# trackuino-shield.net
KiCad netlist of a schematic drawn in EAGLE
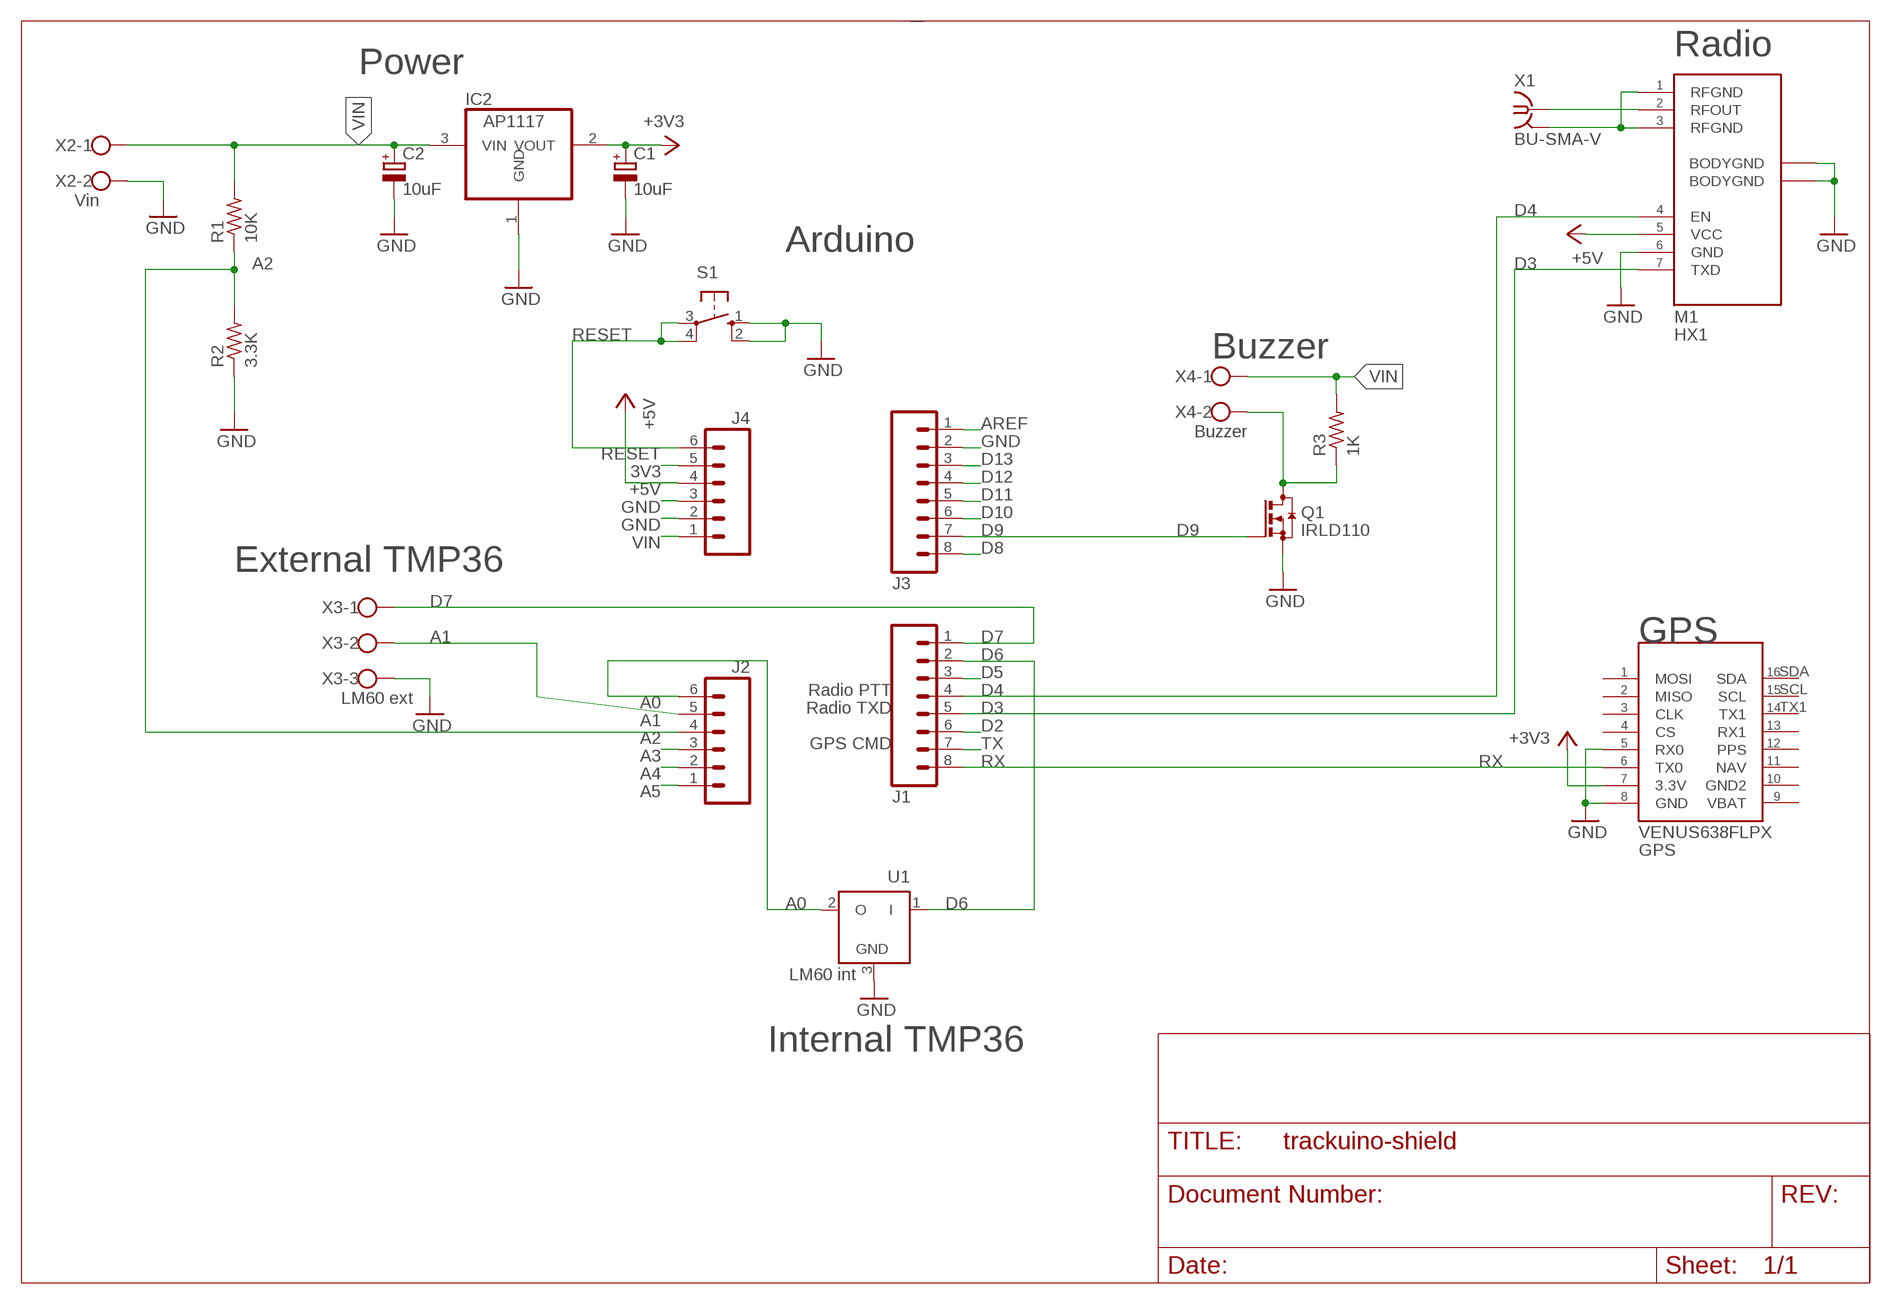
[diagram p0: schematic, sheet 1]

(export (version "E")
  (design (tool "Eeschema 10.0.6"))
  (components
    (comp (ref "C1")
      (value "10uF")
      (footprint "eagle-import:E2,5-5")
      (libsource (lib "eagle-import") (part "CPOL-EUE2.5-5"))
    )
    (comp (ref "C2")
      (value "10uF")
      (footprint "eagle-import:E2,5-5")
      (libsource (lib "eagle-import") (part "CPOL-EUE2.5-5"))
    )
    (comp (ref "GPS")
      (value "VENUS638FLPX")
      (footprint "eagle-import:VENUS638FLPX")
      (libsource (lib "eagle-import") (part "VENUS638FLPX"))
    )
    (comp (ref "IC2")
      (value "AP1117")
      (footprint "eagle-import:TO220-3")
      (libsource (lib "eagle-import") (part "AP1117"))
    )
    (comp (ref "J1")
      (value "M081X08")
      (footprint "eagle-import:1X08")
      (libsource (lib "eagle-import") (part "M081X08"))
    )
    (comp (ref "J2")
      (value "M06SIP")
      (footprint "eagle-import:1X06")
      (libsource (lib "eagle-import") (part "M06SIP"))
    )
    (comp (ref "J3")
      (value "M081X08")
      (footprint "eagle-import:1X08")
      (libsource (lib "eagle-import") (part "M081X08"))
    )
    (comp (ref "J4")
      (value "M06SIP")
      (footprint "eagle-import:1X06")
      (libsource (lib "eagle-import") (part "M06SIP"))
    )
    (comp (ref "M1")
      (value "HX1")
      (footprint "eagle-import:HX1")
      (libsource (lib "eagle-import") (part "HX1"))
    )
    (comp (ref "Q1")
      (value "IRLD110")
      (footprint "eagle-import:HVMDIP")
      (libsource (lib "eagle-import") (part "IRLD110"))
    )
    (comp (ref "R1")
      (value "10K")
      (footprint "eagle-import:0207_7")
      (libsource (lib "eagle-import") (part "R-US_0207/7"))
    )
    (comp (ref "R2")
      (value "3.3K")
      (footprint "eagle-import:0207_7")
      (libsource (lib "eagle-import") (part "R-US_0207/7"))
    )
    (comp (ref "R3")
      (value "1K")
      (footprint "eagle-import:0207_7")
      (libsource (lib "eagle-import") (part "R-US_0207/7"))
    )
    (comp (ref "S1")
      (value "10-XX")
      (footprint "eagle-import:B3F-10XX")
      (libsource (lib "eagle-import") (part "10-XX"))
    )
    (comp (ref "U1")
      (value "LM60 int")
      (footprint "eagle-import:TO92")
      (libsource (lib "eagle-import") (part "LM60"))
    )
    (comp (ref "X1")
      (value "BU-SMA-V")
      (footprint "eagle-import:BU-SMA-V")
      (libsource (lib "eagle-import") (part "BU-SMA-V"))
    )
    (comp (ref "X2")
      (value "Vin")
      (footprint "eagle-import:W237-102")
      (fields (field (name "MPN") "237-102"))
      (libsource (lib "eagle-import") (part "W237-102"))
    )
    (comp (ref "X3")
      (value "LM60 ext")
      (footprint "eagle-import:W237-103")
      (fields (field (name "MPN") "237-103"))
      (libsource (lib "eagle-import") (part "W237-103"))
    )
    (comp (ref "X4")
      (value "Buzzer")
      (footprint "eagle-import:W237-102")
      (fields (field (name "MPN") "237-102"))
      (libsource (lib "eagle-import") (part "W237-102"))
    )
  )
  (nets
    (net (code "1") (name "+3V3") (class "Default")
      (node (ref "C1") (pin "+") (pinfunction "+_+") (pintype "passive"))
      (node (ref "GPS") (pin "3.3V") (pinfunction "3.3V_3.3V") (pintype "bidirectional"))
      (node (ref "IC2") (pin "2") (pinfunction "VOUT_2") (pintype "output"))
    )
    (net (code "2") (name "+5V") (class "Default")
      (node (ref "J4") (pin "4") (pinfunction "4_4") (pintype "passive"))
      (node (ref "M1") (pin "VCC") (pinfunction "VCC_VCC") (pintype "bidirectional"))
    )
    (net (code "3") (name "/3V3") (class "Default")
      (node (ref "J4") (pin "5") (pinfunction "5_5") (pintype "passive"))
    )
    (net (code "4") (name "/A0") (class "Default")
      (node (ref "J2") (pin "6") (pinfunction "6_6") (pintype "passive"))
      (node (ref "U1") (pin "2") (pinfunction "O_2") (pintype "input"))
    )
    (net (code "5") (name "/A1") (class "Default")
      (node (ref "J2") (pin "5") (pinfunction "5_5") (pintype "passive"))
      (node (ref "X3") (pin "2") (pinfunction "KL_2") (pintype "passive"))
    )
    (net (code "6") (name "/A2") (class "Default")
      (node (ref "J2") (pin "4") (pinfunction "4_4") (pintype "passive"))
      (node (ref "R1") (pin "1") (pinfunction "1_1") (pintype "passive"))
      (node (ref "R2") (pin "2") (pinfunction "2_2") (pintype "passive"))
    )
    (net (code "7") (name "/A3") (class "Default")
      (node (ref "J2") (pin "3") (pinfunction "3_3") (pintype "passive"))
    )
    (net (code "8") (name "/A4") (class "Default")
      (node (ref "J2") (pin "2") (pinfunction "2_2") (pintype "passive"))
    )
    (net (code "9") (name "/A5") (class "Default")
      (node (ref "J2") (pin "1") (pinfunction "1_1") (pintype "passive"))
    )
    (net (code "10") (name "/AREF") (class "Default")
      (node (ref "J3") (pin "1") (pinfunction "1_1") (pintype "passive"))
    )
    (net (code "11") (name "/D2") (class "Default")
      (node (ref "J1") (pin "6") (pinfunction "6_6") (pintype "passive"))
    )
    (net (code "12") (name "/D3") (class "Default")
      (node (ref "J1") (pin "5") (pinfunction "5_5") (pintype "passive"))
      (node (ref "M1") (pin "TXD") (pinfunction "TXD_TXD") (pintype "bidirectional"))
    )
    (net (code "13") (name "/D4") (class "Default")
      (node (ref "J1") (pin "4") (pinfunction "4_4") (pintype "passive"))
      (node (ref "M1") (pin "EN") (pinfunction "EN_EN") (pintype "bidirectional"))
    )
    (net (code "14") (name "/D5") (class "Default")
      (node (ref "J1") (pin "3") (pinfunction "3_3") (pintype "passive"))
    )
    (net (code "15") (name "/D6") (class "Default")
      (node (ref "J1") (pin "2") (pinfunction "2_2") (pintype "passive"))
      (node (ref "U1") (pin "1") (pinfunction "I_1") (pintype "input"))
    )
    (net (code "16") (name "/D7") (class "Default")
      (node (ref "J1") (pin "1") (pinfunction "1_1") (pintype "passive"))
      (node (ref "X3") (pin "1") (pinfunction "KL_1") (pintype "passive"))
    )
    (net (code "17") (name "/D8") (class "Default")
      (node (ref "J3") (pin "8") (pinfunction "8_8") (pintype "passive"))
    )
    (net (code "18") (name "/D9") (class "Default")
      (node (ref "J3") (pin "7") (pinfunction "7_7") (pintype "passive"))
      (node (ref "Q1") (pin "G") (pinfunction "G_G") (pintype "passive"))
    )
    (net (code "19") (name "/D10") (class "Default")
      (node (ref "J3") (pin "6") (pinfunction "6_6") (pintype "passive"))
    )
    (net (code "20") (name "/D11") (class "Default")
      (node (ref "J3") (pin "5") (pinfunction "5_5") (pintype "passive"))
    )
    (net (code "21") (name "/D12") (class "Default")
      (node (ref "J3") (pin "4") (pinfunction "4_4") (pintype "passive"))
    )
    (net (code "22") (name "/D13") (class "Default")
      (node (ref "J3") (pin "3") (pinfunction "3_3") (pintype "passive"))
    )
    (net (code "23") (name "/RESET") (class "Default")
      (node (ref "J4") (pin "6") (pinfunction "6_6") (pintype "passive"))
      (node (ref "S1") (pin "3") (pinfunction "P_3") (pintype "passive"))
      (node (ref "S1") (pin "4") (pinfunction "P1_4") (pintype "passive"))
    )
    (net (code "24") (name "/RX") (class "Default")
      (node (ref "GPS") (pin "TX0") (pinfunction "TX0_TX0") (pintype "bidirectional"))
      (node (ref "J1") (pin "8") (pinfunction "8_8") (pintype "passive"))
    )
    (net (code "25") (name "/TX") (class "Default")
      (node (ref "J1") (pin "7") (pinfunction "7_7") (pintype "passive"))
    )
    (net (code "26") (name "GND") (class "Default")
      (node (ref "C1") (pin "-") (pinfunction "-_-") (pintype "passive"))
      (node (ref "C2") (pin "-") (pinfunction "-_-") (pintype "passive"))
      (node (ref "GPS") (pin "GND") (pinfunction "GND_GND") (pintype "bidirectional"))
      (node (ref "GPS") (pin "RX0") (pinfunction "RX0_RX0") (pintype "bidirectional"))
      (node (ref "IC2") (pin "1") (pinfunction "GND_1") (pintype "power_in"))
      (node (ref "J3") (pin "2") (pinfunction "2_2") (pintype "passive"))
      (node (ref "J4") (pin "2") (pinfunction "2_2") (pintype "passive"))
      (node (ref "J4") (pin "3") (pinfunction "3_3") (pintype "passive"))
      (node (ref "M1") (pin "0V") (pinfunction "GND_0V") (pintype "bidirectional"))
      (node (ref "M1") (pin "BODYGND1") (pinfunction "BODYGND_BODYGND1") (pintype "bidirectional"))
      (node (ref "M1") (pin "BODYGND2") (pinfunction "BODYGND_BODYGND2") (pintype "bidirectional"))
      (node (ref "Q1") (pin "S") (pinfunction "S_S") (pintype "passive"))
      (node (ref "R2") (pin "1") (pinfunction "1_1") (pintype "passive"))
      (node (ref "S1") (pin "1") (pinfunction "S_1") (pintype "passive"))
      (node (ref "S1") (pin "2") (pinfunction "S1_2") (pintype "passive"))
      (node (ref "U1") (pin "3") (pinfunction "GND_3") (pintype "power_in"))
      (node (ref "X2") (pin "2") (pinfunction "KL_2") (pintype "passive"))
      (node (ref "X3") (pin "3") (pinfunction "KL_3") (pintype "passive"))
    )
    (net (code "27") (name "Net-(M1-PadRFOUT)") (class "Default")
      (node (ref "M1") (pin "RFOUT") (pinfunction "RFOUT_RFOUT") (pintype "bidirectional"))
      (node (ref "X1") (pin "1") (pinfunction "1_1") (pintype "passive"))
    )
    (net (code "28") (name "Net-(M1-RFGND-PadRFGND1)") (class "Default")
      (node (ref "M1") (pin "RFGND1") (pinfunction "RFGND_RFGND1") (pintype "passive"))
      (node (ref "M1") (pin "RFGND2") (pinfunction "RFGND_RFGND2") (pintype "bidirectional"))
      (node (ref "X1") (pin "2") (pinfunction "2_2") (pintype "passive"))
      (node (ref "X1") (pin "3") (pinfunction "2_3") (pintype "passive"))
      (node (ref "X1") (pin "4") (pinfunction "2_4") (pintype "passive"))
      (node (ref "X1") (pin "5") (pinfunction "2_5") (pintype "passive"))
    )
    (net (code "29") (name "Net-(X4B-KL)") (class "Default")
      (node (ref "Q1") (pin "D@1") (pinfunction "D_D@1") (pintype "passive"))
      (node (ref "Q1") (pin "D@2") (pinfunction "D_D@2") (pintype "passive"))
      (node (ref "R3") (pin "1") (pinfunction "1_1") (pintype "passive"))
      (node (ref "X4") (pin "2") (pinfunction "KL_2") (pintype "passive"))
    )
    (net (code "30") (name "VIN") (class "Default")
      (node (ref "C2") (pin "+") (pinfunction "+_+") (pintype "passive"))
      (node (ref "IC2") (pin "3") (pinfunction "VIN_3") (pintype "input"))
      (node (ref "J4") (pin "1") (pinfunction "1_1") (pintype "passive"))
      (node (ref "R1") (pin "2") (pinfunction "2_2") (pintype "passive"))
      (node (ref "R3") (pin "2") (pinfunction "2_2") (pintype "passive"))
      (node (ref "X2") (pin "1") (pinfunction "KL_1") (pintype "passive"))
      (node (ref "X4") (pin "1") (pinfunction "KL_1") (pintype "passive"))
    )
    (net (code "31") (name "unconnected-(GPS-PadCLK)") (class "Default")
      (node (ref "GPS") (pin "CLK") (pinfunction "CLK_CLK") (pintype "bidirectional"))
    )
    (net (code "32") (name "unconnected-(GPS-PadCS)") (class "Default")
      (node (ref "GPS") (pin "CS") (pinfunction "CS_CS") (pintype "bidirectional"))
    )
    (net (code "33") (name "unconnected-(GPS-PadGND2)") (class "Default")
      (node (ref "GPS") (pin "GND2") (pinfunction "GND2_GND2") (pintype "bidirectional"))
    )
    (net (code "34") (name "unconnected-(GPS-PadMISO)") (class "Default")
      (node (ref "GPS") (pin "MISO") (pinfunction "MISO_MISO") (pintype "bidirectional"))
    )
    (net (code "35") (name "unconnected-(GPS-PadMOSI)") (class "Default")
      (node (ref "GPS") (pin "MOSI") (pinfunction "MOSI_MOSI") (pintype "bidirectional"))
    )
    (net (code "36") (name "unconnected-(GPS-PadNAV)") (class "Default")
      (node (ref "GPS") (pin "NAV") (pinfunction "NAV_NAV") (pintype "bidirectional"))
    )
    (net (code "37") (name "unconnected-(GPS-PadPPS)") (class "Default")
      (node (ref "GPS") (pin "PPS") (pinfunction "PPS_PPS") (pintype "bidirectional"))
    )
    (net (code "38") (name "unconnected-(GPS-PadRX1)") (class "Default")
      (node (ref "GPS") (pin "RX1") (pinfunction "RX1_RX1") (pintype "bidirectional"))
    )
    (net (code "39") (name "unconnected-(GPS-PadSCL)") (class "Default")
      (node (ref "GPS") (pin "SCL") (pinfunction "SCL_SCL") (pintype "bidirectional"))
    )
    (net (code "40") (name "unconnected-(GPS-PadSDA)") (class "Default")
      (node (ref "GPS") (pin "SDA") (pinfunction "SDA_SDA") (pintype "bidirectional"))
    )
    (net (code "41") (name "unconnected-(GPS-PadTX1)") (class "Default")
      (node (ref "GPS") (pin "TX1") (pinfunction "TX1_TX1") (pintype "bidirectional"))
    )
    (net (code "42") (name "unconnected-(GPS-PadVBAT)") (class "Default")
      (node (ref "GPS") (pin "VBAT") (pinfunction "VBAT_VBAT") (pintype "bidirectional"))
    )
  )
)
